# 130827_AriloTX_0_0.net
KiCad netlist of a schematic drawn in EAGLE
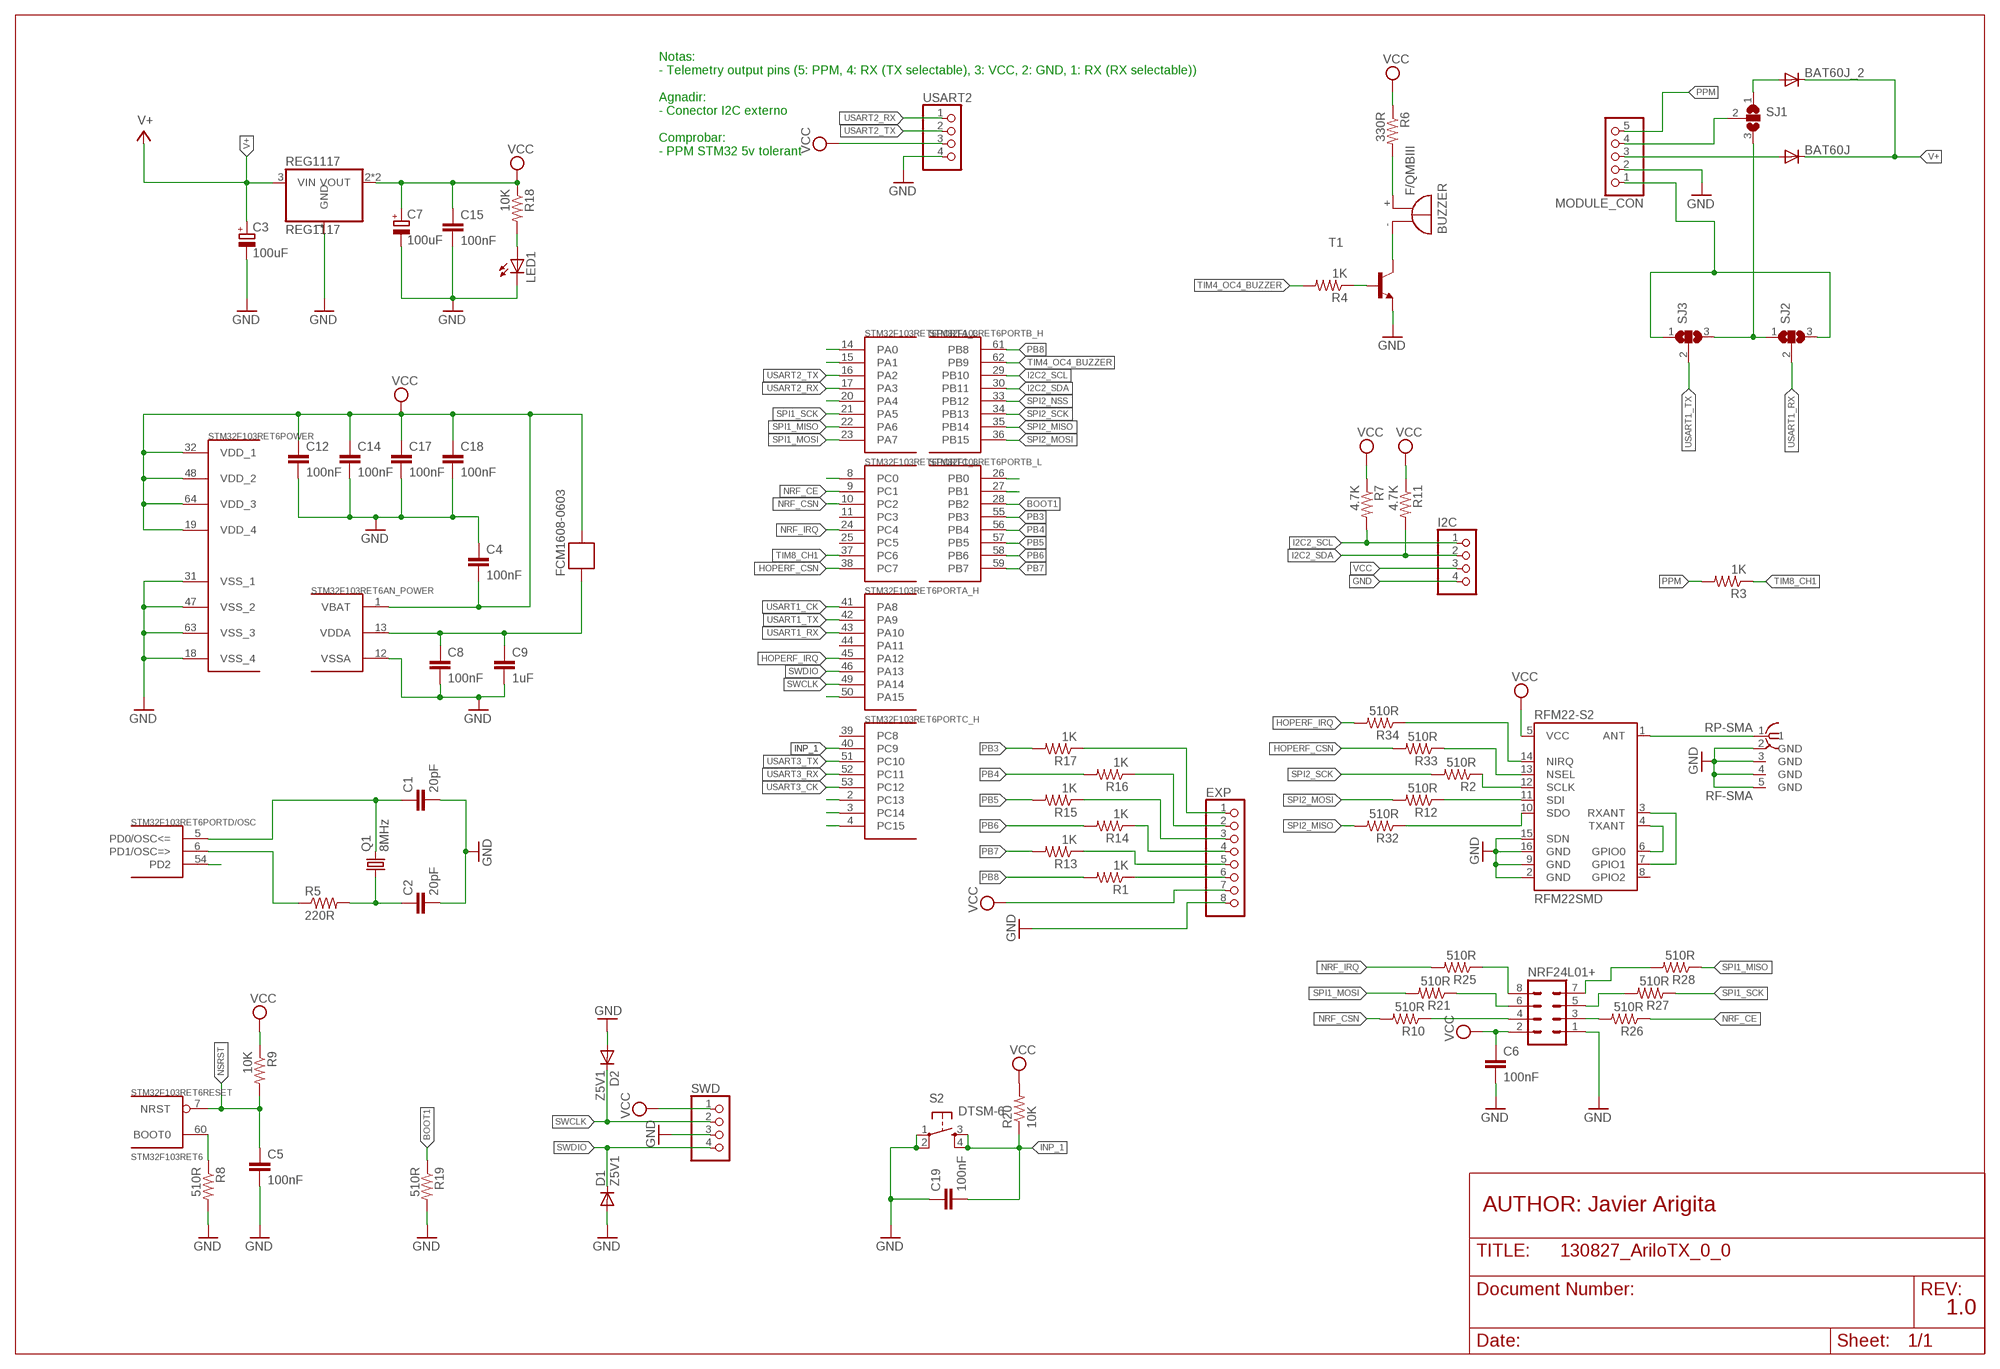
[diagram p0: schematic, sheet 1]

(export (version "E")
  (design (tool "Eeschema 10.0.6"))
  (components
    (comp (ref "BAT60J")
      (value "DIODE-SOD323-R")
      (footprint "eagle-import:SOD323-R")
      (libsource (lib "eagle-import") (part "DIODE-SOD323-R"))
    )
    (comp (ref "BAT60J_2")
      (value "DIODE-SOD323-R")
      (footprint "eagle-import:SOD323-R")
      (libsource (lib "eagle-import") (part "DIODE-SOD323-R"))
    )
    (comp (ref "BUZZER")
      (value "F/QMBIII")
      (footprint "eagle-import:F_QMBIII")
      (libsource (lib "eagle-import") (part "F/QMBIII"))
    )
    (comp (ref "C1")
      (value "20pF")
      (footprint "eagle-import:C0805")
      (libsource (lib "eagle-import") (part "C-EUC0805"))
    )
    (comp (ref "C2")
      (value "20pF")
      (footprint "eagle-import:C0805")
      (libsource (lib "eagle-import") (part "C-EUC0805"))
    )
    (comp (ref "C3")
      (value "100uF")
      (footprint "eagle-import:SMC_B")
      (libsource (lib "eagle-import") (part "CPOL-EUSMCB"))
    )
    (comp (ref "C4")
      (value "100nF")
      (footprint "eagle-import:C0805")
      (libsource (lib "eagle-import") (part "C-EUC0805"))
    )
    (comp (ref "C5")
      (value "100nF")
      (footprint "eagle-import:C0805")
      (libsource (lib "eagle-import") (part "C-EUC0805"))
    )
    (comp (ref "C6")
      (value "100nF")
      (footprint "eagle-import:C0805")
      (libsource (lib "eagle-import") (part "C-EUC0805"))
    )
    (comp (ref "C7")
      (value "100uF")
      (footprint "eagle-import:SMC_B")
      (libsource (lib "eagle-import") (part "CPOL-EUSMCB"))
    )
    (comp (ref "C8")
      (value "100nF")
      (footprint "eagle-import:C0805")
      (libsource (lib "eagle-import") (part "C-EUC0805"))
    )
    (comp (ref "C9")
      (value "1uF")
      (footprint "eagle-import:C3216")
      (libsource (lib "eagle-import") (part "resistor_C-EUC3216"))
    )
    (comp (ref "C12")
      (value "100nF")
      (footprint "eagle-import:C0805")
      (libsource (lib "eagle-import") (part "C-EUC0805"))
    )
    (comp (ref "C14")
      (value "100nF")
      (footprint "eagle-import:C0805")
      (libsource (lib "eagle-import") (part "C-EUC0805"))
    )
    (comp (ref "C15")
      (value "100nF")
      (footprint "eagle-import:C0805")
      (libsource (lib "eagle-import") (part "C-EUC0805"))
    )
    (comp (ref "C17")
      (value "100nF")
      (footprint "eagle-import:C0805")
      (libsource (lib "eagle-import") (part "C-EUC0805"))
    )
    (comp (ref "C18")
      (value "100nF")
      (footprint "eagle-import:C0805")
      (libsource (lib "eagle-import") (part "C-EUC0805"))
    )
    (comp (ref "C19")
      (value "100nF")
      (footprint "eagle-import:C0805")
      (libsource (lib "eagle-import") (part "C-EUC0805"))
    )
    (comp (ref "D1")
      (value "Z5V1")
      (footprint "eagle-import:SOD323-R")
      (libsource (lib "eagle-import") (part "DIODE-SOD323-R"))
    )
    (comp (ref "D2")
      (value "Z5V1")
      (footprint "eagle-import:SOD323-R")
      (libsource (lib "eagle-import") (part "DIODE-SOD323-R"))
    )
    (comp (ref "EXP")
      (value "PINHD-1X8")
      (footprint "eagle-import:1X08")
      (libsource (lib "eagle-import") (part "PINHD-1X8"))
    )
    (comp (ref "FCM1608-0603")
      (value "FERRITE-BEAD")
      (footprint "eagle-import:R0603")
      (libsource (lib "eagle-import") (part "FERRITE-BEAD"))
    )
    (comp (ref "I2C")
      (value "PINHD-1X4")
      (footprint "eagle-import:1X04")
      (libsource (lib "eagle-import") (part "PINHD-1X4"))
    )
    (comp (ref "LED1")
      (value "LED0805")
      (footprint "eagle-import:CHIPLED_0805")
      (libsource (lib "eagle-import") (part "LED0805"))
    )
    (comp (ref "MODULE_CON")
      (value "PINHD-1X5")
      (footprint "eagle-import:1X05")
      (libsource (lib "eagle-import") (part "PINHD-1X5"))
    )
    (comp (ref "NRF24L01+")
      (value "MA04-2")
      (footprint "eagle-import:MA04-2")
      (libsource (lib "eagle-import") (part "MA04-2"))
    )
    (comp (ref "Q1")
      (value "8MHz")
      (footprint "eagle-import:SM49")
      (libsource (lib "eagle-import") (part "CRYSTALSM49"))
    )
    (comp (ref "R1")
      (value "1K")
      (footprint "eagle-import:R0805")
      (libsource (lib "eagle-import") (part "RESISTOR0805"))
    )
    (comp (ref "R2")
      (value "510R")
      (footprint "eagle-import:R0805")
      (libsource (lib "eagle-import") (part "RESISTOR0805"))
    )
    (comp (ref "R3")
      (value "1K")
      (footprint "eagle-import:R0805")
      (libsource (lib "eagle-import") (part "RESISTOR0805"))
    )
    (comp (ref "R4")
      (value "1K")
      (footprint "eagle-import:R0805")
      (libsource (lib "eagle-import") (part "RESISTOR0805"))
    )
    (comp (ref "R5")
      (value "220R")
      (footprint "eagle-import:R0805")
      (libsource (lib "eagle-import") (part "RESISTOR0805"))
    )
    (comp (ref "R6")
      (value "330R")
      (footprint "eagle-import:R0805")
      (libsource (lib "eagle-import") (part "RESISTOR0805"))
    )
    (comp (ref "R7")
      (value "4.7K")
      (footprint "eagle-import:R0805")
      (libsource (lib "eagle-import") (part "RESISTOR0805"))
    )
    (comp (ref "R8")
      (value "510R")
      (footprint "eagle-import:R0805")
      (libsource (lib "eagle-import") (part "RESISTOR0805"))
    )
    (comp (ref "R9")
      (value "10K")
      (footprint "eagle-import:R0805")
      (libsource (lib "eagle-import") (part "RESISTOR0805"))
    )
    (comp (ref "R10")
      (value "510R")
      (footprint "eagle-import:R0805")
      (libsource (lib "eagle-import") (part "RESISTOR0805"))
    )
    (comp (ref "R11")
      (value "4.7K")
      (footprint "eagle-import:R0805")
      (libsource (lib "eagle-import") (part "RESISTOR0805"))
    )
    (comp (ref "R12")
      (value "510R")
      (footprint "eagle-import:R0805")
      (libsource (lib "eagle-import") (part "RESISTOR0805"))
    )
    (comp (ref "R13")
      (value "1K")
      (footprint "eagle-import:R0805")
      (libsource (lib "eagle-import") (part "RESISTOR0805"))
    )
    (comp (ref "R14")
      (value "1K")
      (footprint "eagle-import:R0805")
      (libsource (lib "eagle-import") (part "RESISTOR0805"))
    )
    (comp (ref "R15")
      (value "1K")
      (footprint "eagle-import:R0805")
      (libsource (lib "eagle-import") (part "RESISTOR0805"))
    )
    (comp (ref "R16")
      (value "1K")
      (footprint "eagle-import:R0805")
      (libsource (lib "eagle-import") (part "RESISTOR0805"))
    )
    (comp (ref "R17")
      (value "1K")
      (footprint "eagle-import:R0805")
      (libsource (lib "eagle-import") (part "RESISTOR0805"))
    )
    (comp (ref "R18")
      (value "10K")
      (footprint "eagle-import:R0805")
      (libsource (lib "eagle-import") (part "RESISTOR0805"))
    )
    (comp (ref "R19")
      (value "510R")
      (footprint "eagle-import:R0805")
      (libsource (lib "eagle-import") (part "RESISTOR0805"))
    )
    (comp (ref "R20")
      (value "10K")
      (footprint "eagle-import:R0805")
      (libsource (lib "eagle-import") (part "RESISTOR0805"))
    )
    (comp (ref "R21")
      (value "510R")
      (footprint "eagle-import:R0805")
      (libsource (lib "eagle-import") (part "RESISTOR0805"))
    )
    (comp (ref "R25")
      (value "510R")
      (footprint "eagle-import:R0805")
      (libsource (lib "eagle-import") (part "RESISTOR0805"))
    )
    (comp (ref "R26")
      (value "510R")
      (footprint "eagle-import:R0805")
      (libsource (lib "eagle-import") (part "RESISTOR0805"))
    )
    (comp (ref "R27")
      (value "510R")
      (footprint "eagle-import:R0805")
      (libsource (lib "eagle-import") (part "RESISTOR0805"))
    )
    (comp (ref "R28")
      (value "510R")
      (footprint "eagle-import:R0805")
      (libsource (lib "eagle-import") (part "RESISTOR0805"))
    )
    (comp (ref "R32")
      (value "510R")
      (footprint "eagle-import:R0805")
      (libsource (lib "eagle-import") (part "RESISTOR0805"))
    )
    (comp (ref "R33")
      (value "510R")
      (footprint "eagle-import:R0805")
      (libsource (lib "eagle-import") (part "RESISTOR0805"))
    )
    (comp (ref "R34")
      (value "510R")
      (footprint "eagle-import:R0805")
      (libsource (lib "eagle-import") (part "RESISTOR0805"))
    )
    (comp (ref "REG1117")
      (value "REG1117")
      (footprint "eagle-import:SOT223")
      (libsource (lib "eagle-import") (part "REG1117"))
    )
    (comp (ref "RFM22-S2")
      (value "RFM22SMD")
      (footprint "eagle-import:RFM22-XXX-S2")
      (libsource (lib "eagle-import") (part "RFM22SMD"))
    )
    (comp (ref "RP-SMA")
      (value "RF-SMA")
      (footprint "eagle-import:BU-SMA-H")
      (libsource (lib "eagle-import") (part "RF-SMA"))
    )
    (comp (ref "S2")
      (value "DTSM-6")
      (footprint "eagle-import:DTSM-6")
      (libsource (lib "eagle-import") (part "DTSM-6"))
    )
    (comp (ref "SJ1")
      (value "SJ2W")
      (footprint "eagle-import:SJ_2")
      (libsource (lib "eagle-import") (part "SJ2W"))
    )
    (comp (ref "SJ2")
      (value "SJ2W")
      (footprint "eagle-import:SJ_2")
      (libsource (lib "eagle-import") (part "SJ2W"))
    )
    (comp (ref "SJ3")
      (value "SJ2W")
      (footprint "eagle-import:SJ_2")
      (libsource (lib "eagle-import") (part "SJ2W"))
    )
    (comp (ref "STM32F103RET6")
      (value "STM32F103RET6")
      (footprint "eagle-import:TQFP64")
      (libsource (lib "eagle-import") (part "STM32F10XRXT6"))
    )
    (comp (ref "SWD")
      (value "PINHD-1X4")
      (footprint "eagle-import:1X04")
      (libsource (lib "eagle-import") (part "PINHD-1X4"))
    )
    (comp (ref "T1")
      (value "BC848-NPN-SOT23-BEC")
      (footprint "eagle-import:SOT23-BEC")
      (libsource (lib "eagle-import") (part "-NPN-SOT23-BECBC848"))
    )
    (comp (ref "USART2")
      (value "PINHD-1X4")
      (footprint "eagle-import:1X04")
      (libsource (lib "eagle-import") (part "PINHD-1X4"))
    )
  )
  (nets
    (net (code "1") (name "BOOT1") (class "Default")
      (node (ref "R19") (pin "1") (pinfunction "1_1") (pintype "passive"))
      (node (ref "STM32F103RET6") (pin "28") (pinfunction "PB2_28") (pintype "bidirectional"))
    )
    (net (code "2") (name "GND") (class "Default")
      (node (ref "C1") (pin "2") (pinfunction "2_2") (pintype "passive"))
      (node (ref "C12") (pin "2") (pinfunction "2_2") (pintype "passive"))
      (node (ref "C14") (pin "2") (pinfunction "2_2") (pintype "passive"))
      (node (ref "C15") (pin "2") (pinfunction "2_2") (pintype "passive"))
      (node (ref "C17") (pin "2") (pinfunction "2_2") (pintype "passive"))
      (node (ref "C18") (pin "2") (pinfunction "2_2") (pintype "passive"))
      (node (ref "C19") (pin "1") (pinfunction "1_1") (pintype "passive"))
      (node (ref "C2") (pin "2") (pinfunction "2_2") (pintype "passive"))
      (node (ref "C3") (pin "-") (pinfunction "-_-") (pintype "passive"))
      (node (ref "C4") (pin "1") (pinfunction "1_1") (pintype "passive"))
      (node (ref "C5") (pin "2") (pinfunction "2_2") (pintype "passive"))
      (node (ref "C6") (pin "2") (pinfunction "2_2") (pintype "passive"))
      (node (ref "C7") (pin "-") (pinfunction "-_-") (pintype "passive"))
      (node (ref "C8") (pin "2") (pinfunction "2_2") (pintype "passive"))
      (node (ref "C9") (pin "2") (pinfunction "2_2") (pintype "passive"))
      (node (ref "D1") (pin "A") (pinfunction "A_A") (pintype "passive"))
      (node (ref "D2") (pin "A") (pinfunction "A_A") (pintype "passive"))
      (node (ref "EXP") (pin "8") (pinfunction "8_8") (pintype "passive"))
      (node (ref "I2C") (pin "4") (pinfunction "4_4") (pintype "passive"))
      (node (ref "LED1") (pin "C") (pinfunction "C_C") (pintype "passive"))
      (node (ref "MODULE_CON") (pin "2") (pinfunction "2_2") (pintype "passive"))
      (node (ref "NRF24L01+") (pin "1") (pinfunction "1_1") (pintype "passive"))
      (node (ref "R19") (pin "2") (pinfunction "2_2") (pintype "passive"))
      (node (ref "R8") (pin "2") (pinfunction "2_2") (pintype "passive"))
      (node (ref "REG1117") (pin "1") (pinfunction "GND_1") (pintype "power_in"))
      (node (ref "RFM22-S2") (pin "15") (pinfunction "SDN_15") (pintype "input"))
      (node (ref "RFM22-S2") (pin "16") (pinfunction "GND_16") (pintype "power_in"))
      (node (ref "RFM22-S2") (pin "2") (pinfunction "GND_2") (pintype "power_in"))
      (node (ref "RFM22-S2") (pin "9") (pinfunction "GND_9") (pintype "power_in"))
      (node (ref "RP-SMA") (pin "2") (pinfunction "GND_2") (pintype "power_in"))
      (node (ref "RP-SMA") (pin "3") (pinfunction "GND_3") (pintype "bidirectional"))
      (node (ref "RP-SMA") (pin "4") (pinfunction "GND_4") (pintype "bidirectional"))
      (node (ref "RP-SMA") (pin "5") (pinfunction "GND_5") (pintype "bidirectional"))
      (node (ref "S2") (pin "1") (pinfunction "1_1") (pintype "passive"))
      (node (ref "S2") (pin "2") (pinfunction "2_2") (pintype "passive"))
      (node (ref "STM32F103RET6") (pin "12") (pinfunction "VSSA_12") (pintype "power_in"))
      (node (ref "STM32F103RET6") (pin "18") (pinfunction "VSS_4_18") (pintype "power_in"))
      (node (ref "STM32F103RET6") (pin "31") (pinfunction "VSS_1_31") (pintype "power_in"))
      (node (ref "STM32F103RET6") (pin "47") (pinfunction "VSS_2_47") (pintype "power_in"))
      (node (ref "STM32F103RET6") (pin "63") (pinfunction "VSS_3_63") (pintype "power_in"))
      (node (ref "SWD") (pin "3") (pinfunction "3_3") (pintype "passive"))
      (node (ref "T1") (pin "E") (pinfunction "E_E") (pintype "passive"))
      (node (ref "USART2") (pin "4") (pinfunction "4_4") (pintype "passive"))
    )
    (net (code "3") (name "HOPERF_CSN") (class "Default")
      (node (ref "R33") (pin "2") (pinfunction "2_2") (pintype "passive"))
      (node (ref "STM32F103RET6") (pin "38") (pinfunction "PC7_38") (pintype "bidirectional"))
    )
    (net (code "4") (name "HOPERF_IRQ") (class "Default")
      (node (ref "R34") (pin "2") (pinfunction "2_2") (pintype "passive"))
      (node (ref "STM32F103RET6") (pin "45") (pinfunction "PA12_45") (pintype "bidirectional"))
    )
    (net (code "5") (name "I2C2_SCL") (class "Default")
      (node (ref "I2C") (pin "1") (pinfunction "1_1") (pintype "passive"))
      (node (ref "R7") (pin "2") (pinfunction "2_2") (pintype "passive"))
      (node (ref "STM32F103RET6") (pin "29") (pinfunction "PB10_29") (pintype "bidirectional"))
    )
    (net (code "6") (name "I2C2_SDA") (class "Default")
      (node (ref "I2C") (pin "2") (pinfunction "2_2") (pintype "passive"))
      (node (ref "R11") (pin "2") (pinfunction "2_2") (pintype "passive"))
      (node (ref "STM32F103RET6") (pin "30") (pinfunction "PB11_30") (pintype "bidirectional"))
    )
    (net (code "7") (name "INP_1") (class "Default")
      (node (ref "C19") (pin "2") (pinfunction "2_2") (pintype "passive"))
      (node (ref "R20") (pin "1") (pinfunction "1_1") (pintype "passive"))
      (node (ref "S2") (pin "3") (pinfunction "3_3") (pintype "passive"))
      (node (ref "S2") (pin "4") (pinfunction "4_4") (pintype "passive"))
      (node (ref "STM32F103RET6") (pin "40") (pinfunction "PC9_40") (pintype "bidirectional"))
    )
    (net (code "8") (name "NRF_CE") (class "Default")
      (node (ref "R26") (pin "1") (pinfunction "1_1") (pintype "passive"))
      (node (ref "STM32F103RET6") (pin "9") (pinfunction "PC1_9") (pintype "bidirectional"))
    )
    (net (code "9") (name "NRF_CSN") (class "Default")
      (node (ref "R10") (pin "2") (pinfunction "2_2") (pintype "passive"))
      (node (ref "STM32F103RET6") (pin "10") (pinfunction "PC2_10") (pintype "bidirectional"))
    )
    (net (code "10") (name "NRF_IRQ") (class "Default")
      (node (ref "R25") (pin "2") (pinfunction "2_2") (pintype "passive"))
      (node (ref "STM32F103RET6") (pin "24") (pinfunction "PC4_24") (pintype "bidirectional"))
    )
    (net (code "11") (name "NSRST") (class "Default")
      (node (ref "C5") (pin "1") (pinfunction "1_1") (pintype "passive"))
      (node (ref "R9") (pin "2") (pinfunction "2_2") (pintype "passive"))
      (node (ref "STM32F103RET6") (pin "7") (pinfunction "NRST_7") (pintype "input"))
    )
    (net (code "12") (name "Net-(BAT60J-PadA)") (class "Default")
      (node (ref "BAT60J") (pin "A") (pinfunction "A_A") (pintype "passive"))
      (node (ref "MODULE_CON") (pin "3") (pinfunction "3_3") (pintype "passive"))
    )
    (net (code "13") (name "Net-(BAT60J_2-PadA)") (class "Default")
      (node (ref "BAT60J_2") (pin "A") (pinfunction "A_A") (pintype "passive"))
      (node (ref "SJ1") (pin "1") (pinfunction "1_1") (pintype "passive"))
    )
    (net (code "14") (name "Net-(BUZZER-+)") (class "Default")
      (node (ref "BUZZER") (pin "-") (pinfunction "+_-") (pintype "passive"))
      (node (ref "T1") (pin "C") (pinfunction "C_C") (pintype "passive"))
    )
    (net (code "15") (name "Net-(BUZZER--)") (class "Default")
      (node (ref "BUZZER") (pin "+") (pinfunction "-_+") (pintype "passive"))
      (node (ref "R6") (pin "2") (pinfunction "2_2") (pintype "passive"))
    )
    (net (code "16") (name "Net-(C2-Pad1)") (class "Default")
      (node (ref "C2") (pin "1") (pinfunction "1_1") (pintype "passive"))
      (node (ref "Q1") (pin "1") (pinfunction "1_1") (pintype "passive"))
      (node (ref "R5") (pin "2") (pinfunction "2_2") (pintype "passive"))
    )
    (net (code "17") (name "Net-(EXP-Pad1)") (class "Default")
      (node (ref "EXP") (pin "1") (pinfunction "1_1") (pintype "passive"))
      (node (ref "R17") (pin "1") (pinfunction "1_1") (pintype "passive"))
    )
    (net (code "18") (name "Net-(EXP-Pad2)") (class "Default")
      (node (ref "EXP") (pin "2") (pinfunction "2_2") (pintype "passive"))
      (node (ref "R16") (pin "1") (pinfunction "1_1") (pintype "passive"))
    )
    (net (code "19") (name "Net-(EXP-Pad3)") (class "Default")
      (node (ref "EXP") (pin "3") (pinfunction "3_3") (pintype "passive"))
      (node (ref "R15") (pin "1") (pinfunction "1_1") (pintype "passive"))
    )
    (net (code "20") (name "Net-(EXP-Pad4)") (class "Default")
      (node (ref "EXP") (pin "4") (pinfunction "4_4") (pintype "passive"))
      (node (ref "R14") (pin "1") (pinfunction "1_1") (pintype "passive"))
    )
    (net (code "21") (name "Net-(EXP-Pad5)") (class "Default")
      (node (ref "EXP") (pin "5") (pinfunction "5_5") (pintype "passive"))
      (node (ref "R13") (pin "1") (pinfunction "1_1") (pintype "passive"))
    )
    (net (code "22") (name "Net-(EXP-Pad6)") (class "Default")
      (node (ref "EXP") (pin "6") (pinfunction "6_6") (pintype "passive"))
      (node (ref "R1") (pin "1") (pinfunction "1_1") (pintype "passive"))
    )
    (net (code "23") (name "Net-(FCM1608-0603-P$2)") (class "Default")
      (node (ref "C8") (pin "1") (pinfunction "1_1") (pintype "passive"))
      (node (ref "C9") (pin "1") (pinfunction "1_1") (pintype "passive"))
      (node (ref "FCM1608-0603") (pin "2") (pinfunction "P$2_2") (pintype "bidirectional"))
      (node (ref "STM32F103RET6") (pin "13") (pinfunction "VDDA_13") (pintype "power_in"))
    )
    (net (code "24") (name "Net-(LED1-PadA)") (class "Default")
      (node (ref "LED1") (pin "A") (pinfunction "A_A") (pintype "passive"))
      (node (ref "R18") (pin "2") (pinfunction "2_2") (pintype "passive"))
    )
    (net (code "25") (name "Net-(MODULE_CON-Pad1)") (class "Default")
      (node (ref "MODULE_CON") (pin "1") (pinfunction "1_1") (pintype "passive"))
      (node (ref "SJ2") (pin "3") (pinfunction "3_3") (pintype "passive"))
      (node (ref "SJ3") (pin "1") (pinfunction "1_1") (pintype "passive"))
    )
    (net (code "26") (name "Net-(MODULE_CON-Pad4)") (class "Default")
      (node (ref "MODULE_CON") (pin "4") (pinfunction "4_4") (pintype "passive"))
      (node (ref "SJ1") (pin "2") (pinfunction "2_2") (pintype "passive"))
    )
    (net (code "27") (name "Net-(NRF24L01+-Pad3)") (class "Default")
      (node (ref "NRF24L01+") (pin "3") (pinfunction "3_3") (pintype "passive"))
      (node (ref "R26") (pin "2") (pinfunction "2_2") (pintype "passive"))
    )
    (net (code "28") (name "Net-(NRF24L01+-Pad4)") (class "Default")
      (node (ref "NRF24L01+") (pin "4") (pinfunction "4_4") (pintype "passive"))
      (node (ref "R10") (pin "1") (pinfunction "1_1") (pintype "passive"))
    )
    (net (code "29") (name "Net-(NRF24L01+-Pad5)") (class "Default")
      (node (ref "NRF24L01+") (pin "5") (pinfunction "5_5") (pintype "passive"))
      (node (ref "R27") (pin "2") (pinfunction "2_2") (pintype "passive"))
    )
    (net (code "30") (name "Net-(NRF24L01+-Pad6)") (class "Default")
      (node (ref "NRF24L01+") (pin "6") (pinfunction "6_6") (pintype "passive"))
      (node (ref "R21") (pin "1") (pinfunction "1_1") (pintype "passive"))
    )
    (net (code "31") (name "Net-(NRF24L01+-Pad7)") (class "Default")
      (node (ref "NRF24L01+") (pin "7") (pinfunction "7_7") (pintype "passive"))
      (node (ref "R28") (pin "2") (pinfunction "2_2") (pintype "passive"))
    )
    (net (code "32") (name "Net-(NRF24L01+-Pad8)") (class "Default")
      (node (ref "NRF24L01+") (pin "8") (pinfunction "8_8") (pintype "passive"))
      (node (ref "R25") (pin "1") (pinfunction "1_1") (pintype "passive"))
    )
    (net (code "33") (name "Net-(R4-Pad1)") (class "Default")
      (node (ref "R4") (pin "1") (pinfunction "1_1") (pintype "passive"))
      (node (ref "T1") (pin "B") (pinfunction "B_B") (pintype "passive"))
    )
    (net (code "34") (name "Net-(RFM22-S2-ANT)") (class "Default")
      (node (ref "RFM22-S2") (pin "1") (pinfunction "ANT_1") (pintype "bidirectional"))
      (node (ref "RP-SMA") (pin "1") (pinfunction "1_1") (pintype "passive"))
    )
    (net (code "35") (name "Net-(RFM22-S2-GPIO0)") (class "Default")
      (node (ref "RFM22-S2") (pin "4") (pinfunction "TXANT_4") (pintype "input"))
      (node (ref "RFM22-S2") (pin "6") (pinfunction "GPIO0_6") (pintype "bidirectional"))
    )
    (net (code "36") (name "Net-(RFM22-S2-GPIO1)") (class "Default")
      (node (ref "RFM22-S2") (pin "3") (pinfunction "RXANT_3") (pintype "input"))
      (node (ref "RFM22-S2") (pin "7") (pinfunction "GPIO1_7") (pintype "bidirectional"))
    )
    (net (code "37") (name "Net-(RFM22-S2-NIRQ)") (class "Default")
      (node (ref "R34") (pin "1") (pinfunction "1_1") (pintype "passive"))
      (node (ref "RFM22-S2") (pin "14") (pinfunction "NIRQ_14") (pintype "output"))
    )
    (net (code "38") (name "Net-(RFM22-S2-NSEL)") (class "Default")
      (node (ref "R33") (pin "1") (pinfunction "1_1") (pintype "passive"))
      (node (ref "RFM22-S2") (pin "13") (pinfunction "NSEL_13") (pintype "input"))
    )
    (net (code "39") (name "Net-(RFM22-S2-SCLK)") (class "Default")
      (node (ref "R2") (pin "1") (pinfunction "1_1") (pintype "passive"))
      (node (ref "RFM22-S2") (pin "12") (pinfunction "SCLK_12") (pintype "input"))
    )
    (net (code "40") (name "Net-(RFM22-S2-SDI)") (class "Default")
      (node (ref "R12") (pin "1") (pinfunction "1_1") (pintype "passive"))
      (node (ref "RFM22-S2") (pin "11") (pinfunction "SDI_11") (pintype "input"))
    )
    (net (code "41") (name "Net-(RFM22-S2-SDO)") (class "Default")
      (node (ref "R32") (pin "1") (pinfunction "1_1") (pintype "passive"))
      (node (ref "RFM22-S2") (pin "10") (pinfunction "SDO_10") (pintype "output"))
    )
    (net (code "42") (name "Net-(SJ1-Pad3)") (class "Default")
      (node (ref "SJ1") (pin "3") (pinfunction "3_3") (pintype "passive"))
      (node (ref "SJ2") (pin "1") (pinfunction "1_1") (pintype "passive"))
      (node (ref "SJ3") (pin "3") (pinfunction "3_3") (pintype "passive"))
    )
    (net (code "43") (name "Net-(STM32F103RET6H-PD0{slash}OSC<=)") (class "Default")
      (node (ref "C1") (pin "1") (pinfunction "1_1") (pintype "passive"))
      (node (ref "Q1") (pin "2") (pinfunction "2_2") (pintype "passive"))
      (node (ref "STM32F103RET6") (pin "5") (pinfunction "PD0/OSC<=_5") (pintype "bidirectional"))
    )
    (net (code "44") (name "Net-(STM32F103RET6H-PD1{slash}OSC=>)") (class "Default")
      (node (ref "R5") (pin "1") (pinfunction "1_1") (pintype "passive"))
      (node (ref "STM32F103RET6") (pin "6") (pinfunction "PD1/OSC=>_6") (pintype "bidirectional"))
    )
    (net (code "45") (name "Net-(STM32F103RET6J-BOOT0)") (class "Default")
      (node (ref "R8") (pin "1") (pinfunction "1_1") (pintype "passive"))
      (node (ref "STM32F103RET6") (pin "60") (pinfunction "BOOT0_60") (pintype "input"))
    )
    (net (code "46") (name "PB3") (class "Default")
      (node (ref "R17") (pin "2") (pinfunction "2_2") (pintype "passive"))
      (node (ref "STM32F103RET6") (pin "55") (pinfunction "PB3_55") (pintype "bidirectional"))
    )
    (net (code "47") (name "PB4") (class "Default")
      (node (ref "R16") (pin "2") (pinfunction "2_2") (pintype "passive"))
      (node (ref "STM32F103RET6") (pin "56") (pinfunction "PB4_56") (pintype "bidirectional"))
    )
    (net (code "48") (name "PB5") (class "Default")
      (node (ref "R15") (pin "2") (pinfunction "2_2") (pintype "passive"))
      (node (ref "STM32F103RET6") (pin "57") (pinfunction "PB5_57") (pintype "bidirectional"))
    )
    (net (code "49") (name "PB6") (class "Default")
      (node (ref "R14") (pin "2") (pinfunction "2_2") (pintype "passive"))
      (node (ref "STM32F103RET6") (pin "58") (pinfunction "PB6_58") (pintype "bidirectional"))
    )
    (net (code "50") (name "PB7") (class "Default")
      (node (ref "R13") (pin "2") (pinfunction "2_2") (pintype "passive"))
      (node (ref "STM32F103RET6") (pin "59") (pinfunction "PB7_59") (pintype "bidirectional"))
    )
    (net (code "51") (name "PB8") (class "Default")
      (node (ref "R1") (pin "2") (pinfunction "2_2") (pintype "passive"))
      (node (ref "STM32F103RET6") (pin "61") (pinfunction "PB8_61") (pintype "bidirectional"))
    )
    (net (code "52") (name "PPM") (class "Default")
      (node (ref "MODULE_CON") (pin "5") (pinfunction "5_5") (pintype "passive"))
      (node (ref "R3") (pin "2") (pinfunction "2_2") (pintype "passive"))
    )
    (net (code "53") (name "SPI1_MISO") (class "Default")
      (node (ref "R28") (pin "1") (pinfunction "1_1") (pintype "passive"))
      (node (ref "STM32F103RET6") (pin "22") (pinfunction "PA6_22") (pintype "bidirectional"))
    )
    (net (code "54") (name "SPI1_MOSI") (class "Default")
      (node (ref "R21") (pin "2") (pinfunction "2_2") (pintype "passive"))
      (node (ref "STM32F103RET6") (pin "23") (pinfunction "PA7_23") (pintype "bidirectional"))
    )
    (net (code "55") (name "SPI1_SCK") (class "Default")
      (node (ref "R27") (pin "1") (pinfunction "1_1") (pintype "passive"))
      (node (ref "STM32F103RET6") (pin "21") (pinfunction "PA5_21") (pintype "bidirectional"))
    )
    (net (code "56") (name "SPI2_MISO") (class "Default")
      (node (ref "R32") (pin "2") (pinfunction "2_2") (pintype "passive"))
      (node (ref "STM32F103RET6") (pin "35") (pinfunction "PB14_35") (pintype "bidirectional"))
    )
    (net (code "57") (name "SPI2_MOSI") (class "Default")
      (node (ref "R12") (pin "2") (pinfunction "2_2") (pintype "passive"))
      (node (ref "STM32F103RET6") (pin "36") (pinfunction "PB15_36") (pintype "bidirectional"))
    )
    (net (code "58") (name "SPI2_NSS") (class "Default")
      (node (ref "STM32F103RET6") (pin "33") (pinfunction "PB12_33") (pintype "bidirectional"))
    )
    (net (code "59") (name "SPI2_SCK") (class "Default")
      (node (ref "R2") (pin "2") (pinfunction "2_2") (pintype "passive"))
      (node (ref "STM32F103RET6") (pin "34") (pinfunction "PB13_34") (pintype "bidirectional"))
    )
    (net (code "60") (name "SWCLK") (class "Default")
      (node (ref "D2") (pin "C") (pinfunction "C_C") (pintype "passive"))
      (node (ref "STM32F103RET6") (pin "49") (pinfunction "PA14_49") (pintype "bidirectional"))
      (node (ref "SWD") (pin "2") (pinfunction "2_2") (pintype "passive"))
    )
    (net (code "61") (name "SWDIO") (class "Default")
      (node (ref "D1") (pin "C") (pinfunction "C_C") (pintype "passive"))
      (node (ref "STM32F103RET6") (pin "46") (pinfunction "PA13_46") (pintype "bidirectional"))
      (node (ref "SWD") (pin "4") (pinfunction "4_4") (pintype "passive"))
    )
    (net (code "62") (name "TIM4_OC4_BUZZER") (class "Default")
      (node (ref "R4") (pin "2") (pinfunction "2_2") (pintype "passive"))
      (node (ref "STM32F103RET6") (pin "62") (pinfunction "PB9_62") (pintype "bidirectional"))
    )
    (net (code "63") (name "TIM8_CH1") (class "Default")
      (node (ref "R3") (pin "1") (pinfunction "1_1") (pintype "passive"))
      (node (ref "STM32F103RET6") (pin "37") (pinfunction "PC6_37") (pintype "bidirectional"))
    )
    (net (code "64") (name "USART1_CK") (class "Default")
      (node (ref "STM32F103RET6") (pin "41") (pinfunction "PA8_41") (pintype "bidirectional"))
    )
    (net (code "65") (name "USART1_RX") (class "Default")
      (node (ref "SJ2") (pin "2") (pinfunction "2_2") (pintype "passive"))
      (node (ref "STM32F103RET6") (pin "43") (pinfunction "PA10_43") (pintype "bidirectional"))
    )
    (net (code "66") (name "USART1_TX") (class "Default")
      (node (ref "SJ3") (pin "2") (pinfunction "2_2") (pintype "passive"))
      (node (ref "STM32F103RET6") (pin "42") (pinfunction "PA9_42") (pintype "bidirectional"))
    )
    (net (code "67") (name "USART2_RX") (class "Default")
      (node (ref "STM32F103RET6") (pin "17") (pinfunction "PA3_17") (pintype "bidirectional"))
      (node (ref "USART2") (pin "1") (pinfunction "1_1") (pintype "passive"))
    )
    (net (code "68") (name "USART2_TX") (class "Default")
      (node (ref "STM32F103RET6") (pin "16") (pinfunction "PA2_16") (pintype "bidirectional"))
      (node (ref "USART2") (pin "2") (pinfunction "2_2") (pintype "passive"))
    )
    (net (code "69") (name "USART3_CK") (class "Default")
      (node (ref "STM32F103RET6") (pin "53") (pinfunction "PC12_53") (pintype "bidirectional"))
    )
    (net (code "70") (name "USART3_RX") (class "Default")
      (node (ref "STM32F103RET6") (pin "52") (pinfunction "PC11_52") (pintype "bidirectional"))
    )
    (net (code "71") (name "USART3_TX") (class "Default")
      (node (ref "STM32F103RET6") (pin "51") (pinfunction "PC10_51") (pintype "bidirectional"))
    )
    (net (code "72") (name "V+") (class "Default")
      (node (ref "BAT60J") (pin "C") (pinfunction "C_C") (pintype "passive"))
      (node (ref "BAT60J_2") (pin "C") (pinfunction "C_C") (pintype "passive"))
      (node (ref "C3") (pin "+") (pinfunction "+_+") (pintype "passive"))
      (node (ref "REG1117") (pin "3") (pinfunction "VIN_3") (pintype "input"))
    )
    (net (code "73") (name "VCC") (class "Default")
      (node (ref "C12") (pin "1") (pinfunction "1_1") (pintype "passive"))
      (node (ref "C14") (pin "1") (pinfunction "1_1") (pintype "passive"))
      (node (ref "C15") (pin "1") (pinfunction "1_1") (pintype "passive"))
      (node (ref "C17") (pin "1") (pinfunction "1_1") (pintype "passive"))
      (node (ref "C18") (pin "1") (pinfunction "1_1") (pintype "passive"))
      (node (ref "C4") (pin "2") (pinfunction "2_2") (pintype "passive"))
      (node (ref "C6") (pin "1") (pinfunction "1_1") (pintype "passive"))
      (node (ref "C7") (pin "+") (pinfunction "+_+") (pintype "passive"))
      (node (ref "EXP") (pin "7") (pinfunction "7_7") (pintype "passive"))
      (node (ref "FCM1608-0603") (pin "1") (pinfunction "P$1_1") (pintype "bidirectional"))
      (node (ref "I2C") (pin "3") (pinfunction "3_3") (pintype "passive"))
      (node (ref "NRF24L01+") (pin "2") (pinfunction "2_2") (pintype "passive"))
      (node (ref "R11") (pin "1") (pinfunction "1_1") (pintype "passive"))
      (node (ref "R18") (pin "1") (pinfunction "1_1") (pintype "passive"))
      (node (ref "R20") (pin "2") (pinfunction "2_2") (pintype "passive"))
      (node (ref "R6") (pin "1") (pinfunction "1_1") (pintype "passive"))
      (node (ref "R7") (pin "1") (pinfunction "1_1") (pintype "passive"))
      (node (ref "R9") (pin "1") (pinfunction "1_1") (pintype "passive"))
      (node (ref "REG1117") (pin "2") (pinfunction "VOUT_2") (pintype "power_in"))
      (node (ref "REG1117") (pin "4") (pinfunction "VOUT_4") (pintype "power_in"))
      (node (ref "RFM22-S2") (pin "5") (pinfunction "VCC_5") (pintype "bidirectional"))
      (node (ref "STM32F103RET6") (pin "1") (pinfunction "VBAT_1") (pintype "power_in"))
      (node (ref "STM32F103RET6") (pin "19") (pinfunction "VDD_4_19") (pintype "power_in"))
      (node (ref "STM32F103RET6") (pin "32") (pinfunction "VDD_1_32") (pintype "power_in"))
      (node (ref "STM32F103RET6") (pin "48") (pinfunction "VDD_2_48") (pintype "power_in"))
      (node (ref "STM32F103RET6") (pin "64") (pinfunction "VDD_3_64") (pintype "power_in"))
      (node (ref "SWD") (pin "1") (pinfunction "1_1") (pintype "passive"))
      (node (ref "USART2") (pin "3") (pinfunction "3_3") (pintype "passive"))
    )
    (net (code "74") (name "unconnected-(RFM22-S2-GPIO2-Pad8)") (class "Default")
      (node (ref "RFM22-S2") (pin "8") (pinfunction "GPIO2_8") (pintype "bidirectional"))
    )
    (net (code "75") (name "unconnected-(STM32F103RET6B-PA11-Pad44)") (class "Default")
      (node (ref "STM32F103RET6") (pin "44") (pinfunction "PA11_44") (pintype "bidirectional"))
    )
    (net (code "76") (name "unconnected-(STM32F103RET6B-PA15-Pad50)") (class "Default")
      (node (ref "STM32F103RET6") (pin "50") (pinfunction "PA15_50") (pintype "bidirectional"))
    )
    (net (code "77") (name "unconnected-(STM32F103RET6C-PA0-Pad14)") (class "Default")
      (node (ref "STM32F103RET6") (pin "14") (pinfunction "PA0_14") (pintype "bidirectional"))
    )
    (net (code "78") (name "unconnected-(STM32F103RET6C-PA1-Pad15)") (class "Default")
      (node (ref "STM32F103RET6") (pin "15") (pinfunction "PA1_15") (pintype "bidirectional"))
    )
    (net (code "79") (name "unconnected-(STM32F103RET6C-PA4-Pad20)") (class "Default")
      (node (ref "STM32F103RET6") (pin "20") (pinfunction "PA4_20") (pintype "bidirectional"))
    )
    (net (code "80") (name "unconnected-(STM32F103RET6E-PB0-Pad26)") (class "Default")
      (node (ref "STM32F103RET6") (pin "26") (pinfunction "PB0_26") (pintype "bidirectional"))
    )
    (net (code "81") (name "unconnected-(STM32F103RET6E-PB1-Pad27)") (class "Default")
      (node (ref "STM32F103RET6") (pin "27") (pinfunction "PB1_27") (pintype "bidirectional"))
    )
    (net (code "82") (name "unconnected-(STM32F103RET6F-PC8-Pad39)") (class "Default")
      (node (ref "STM32F103RET6") (pin "39") (pinfunction "PC8_39") (pintype "bidirectional"))
    )
    (net (code "83") (name "unconnected-(STM32F103RET6F-PC13-Pad2)") (class "Default")
      (node (ref "STM32F103RET6") (pin "2") (pinfunction "PC13_2") (pintype "bidirectional"))
    )
    (net (code "84") (name "unconnected-(STM32F103RET6F-PC14-Pad3)") (class "Default")
      (node (ref "STM32F103RET6") (pin "3") (pinfunction "PC14_3") (pintype "bidirectional"))
    )
    (net (code "85") (name "unconnected-(STM32F103RET6F-PC15-Pad4)") (class "Default")
      (node (ref "STM32F103RET6") (pin "4") (pinfunction "PC15_4") (pintype "bidirectional"))
    )
    (net (code "86") (name "unconnected-(STM32F103RET6G-PC0-Pad8)") (class "Default")
      (node (ref "STM32F103RET6") (pin "8") (pinfunction "PC0_8") (pintype "bidirectional"))
    )
    (net (code "87") (name "unconnected-(STM32F103RET6G-PC3-Pad11)") (class "Default")
      (node (ref "STM32F103RET6") (pin "11") (pinfunction "PC3_11") (pintype "bidirectional"))
    )
    (net (code "88") (name "unconnected-(STM32F103RET6G-PC5-Pad25)") (class "Default")
      (node (ref "STM32F103RET6") (pin "25") (pinfunction "PC5_25") (pintype "bidirectional"))
    )
    (net (code "89") (name "unconnected-(STM32F103RET6H-PD2-Pad54)") (class "Default")
      (node (ref "STM32F103RET6") (pin "54") (pinfunction "PD2_54") (pintype "bidirectional"))
    )
  )
)
